# LCD_Display.net
KiCad netlist of a schematic drawn in Altium Designer
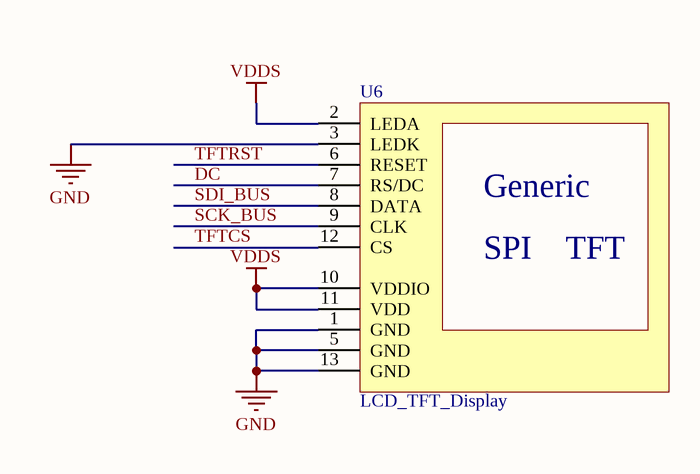
[diagram p0: LCD_Display.SchDoc]

(export (version "E")
  (design (tool "Eeschema 10.0.6"))
  (components
    (comp (ref "U6")
      (value "LCD_TFT_Display")
      (footprint "LCD_Ribbon")
      (libsource (lib "Biosense_Altium_Library") (part "LCD_TFT_Display"))
    )
  )
  (nets
    (net (code "1") (name "/DC") (class "Default")
      (node (ref "U6") (pin "7") (pinfunction "RS/DC_7") (pintype "passive"))
    )
    (net (code "2") (name "/SCK_BUS") (class "Default")
      (node (ref "U6") (pin "9") (pinfunction "CLK_9") (pintype "passive"))
    )
    (net (code "3") (name "/SDI_BUS") (class "Default")
      (node (ref "U6") (pin "8") (pinfunction "DATA_8") (pintype "passive"))
    )
    (net (code "4") (name "/TFTCS") (class "Default")
      (node (ref "U6") (pin "12") (pinfunction "CS_12") (pintype "passive"))
    )
    (net (code "5") (name "/~{TFTRST}") (class "Default")
      (node (ref "U6") (pin "6") (pinfunction "RESET_6") (pintype "passive"))
    )
    (net (code "6") (name "GND") (class "Default")
      (node (ref "U6") (pin "1") (pinfunction "GND_1") (pintype "passive"))
      (node (ref "U6") (pin "13") (pinfunction "GND_13") (pintype "passive"))
      (node (ref "U6") (pin "3") (pinfunction "LEDK_3") (pintype "passive"))
      (node (ref "U6") (pin "5") (pinfunction "GND_5") (pintype "passive"))
    )
    (net (code "7") (name "VDDS") (class "Default")
      (node (ref "U6") (pin "10") (pinfunction "VDDIO_10") (pintype "passive"))
      (node (ref "U6") (pin "11") (pinfunction "VDD_11") (pintype "passive"))
      (node (ref "U6") (pin "2") (pinfunction "LEDA_2") (pintype "passive"))
    )
  )
)
